# door_FM_rev_C.net
KiCad netlist of a schematic drawn in EAGLE
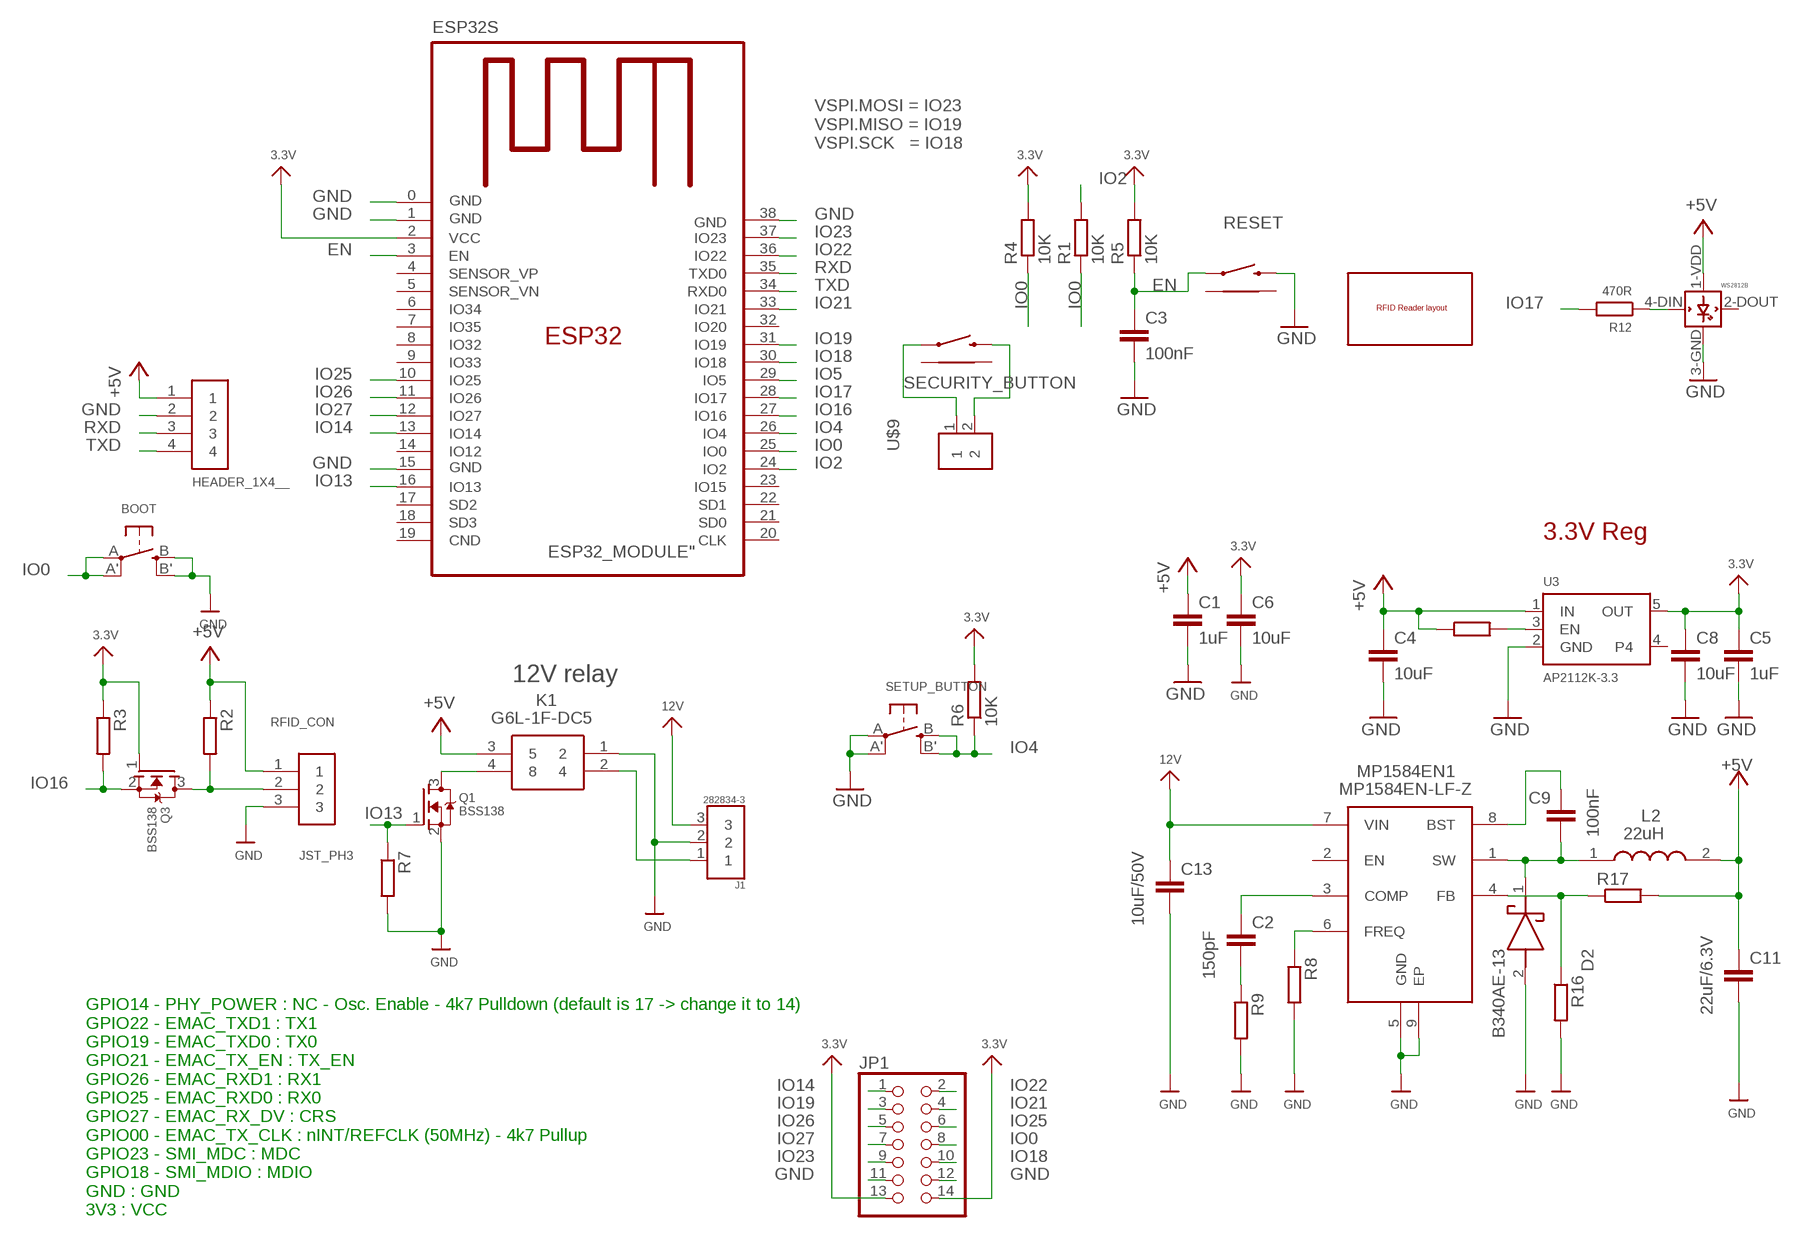
[diagram p0: schematic, sheet 1]

(export (version "E")
  (design (tool "Eeschema 10.0.6"))
  (components
    (comp (ref "BOOT")
      (value "BUTTON_KMR2_4.6X2.8")
      (footprint "eagle-import:BUTTON_KMR2_4.6X2.8")
      (libsource (lib "eagle-import") (part "BUTTON_KMR2_4.6X2.8"))
    )
    (comp (ref "C1")
      (value "1uF")
      (footprint "eagle-import:C0805")
      (libsource (lib "eagle-import") (part "C-EUC0805"))
    )
    (comp (ref "C2")
      (value "150pF")
      (footprint "eagle-import:C0805")
      (libsource (lib "eagle-import") (part "C-EUC0805"))
    )
    (comp (ref "C3")
      (value "100nF")
      (footprint "eagle-import:C0805")
      (libsource (lib "eagle-import") (part "C-EUC0805"))
    )
    (comp (ref "C4")
      (value "10uF")
      (footprint "eagle-import:C0805")
      (libsource (lib "eagle-import") (part "C-EUC0805"))
    )
    (comp (ref "C5")
      (value "1uF")
      (footprint "eagle-import:C0805")
      (libsource (lib "eagle-import") (part "C-EUC0805"))
    )
    (comp (ref "C6")
      (value "10uF")
      (footprint "eagle-import:C0805")
      (libsource (lib "eagle-import") (part "C-EUC0805"))
    )
    (comp (ref "C8")
      (value "10uF")
      (footprint "eagle-import:C0805")
      (libsource (lib "eagle-import") (part "C-EUC0805"))
    )
    (comp (ref "C9")
      (value "100nF")
      (footprint "eagle-import:C0805")
      (libsource (lib "eagle-import") (part "C-EUC0805"))
    )
    (comp (ref "C11")
      (value "22uF/6.3V")
      (footprint "eagle-import:C0805")
      (libsource (lib "eagle-import") (part "C-EUC0805"))
    )
    (comp (ref "C13")
      (value "10uF/50V")
      (footprint "eagle-import:C1206")
      (libsource (lib "eagle-import") (part "C-EUC1206"))
    )
    (comp (ref "CN1")
      (value "HEADER_1X4__")
      (footprint "eagle-import:HEADER_1X4_RIGHT_ANGLE")
      (libsource (lib "eagle-import") (part "HEADER_1X4__"))
    )
    (comp (ref "D2")
      (value "B340AE-13")
      (footprint "eagle-import:DIOM5226X240N")
      (fields (field (name "MOUSER_PART_NUMBER") "621-B340AE-13"))
      (libsource (lib "eagle-import") (part "B340AE-13"))
    )
    (comp (ref "ESP32S")
      (value "ESP32_MODULE\"")
      (footprint "eagle-import:ESP32_MODULE")
      (libsource (lib "eagle-import") (part "ESP32_MODULE{dblquote}"))
    )
    (comp (ref "J1")
      (value "282834-3")
      (footprint "eagle-import:TE_282834-3")
      (fields (field (name "MF") "TE Connectivity"))
      (libsource (lib "eagle-import") (part "282834-3"))
    )
    (comp (ref "JP1")
      (value "PINHD-2X7SMT")
      (footprint "eagle-import:2X07_SMT")
      (libsource (lib "eagle-import") (part "PINHD-2X7SMT"))
    )
    (comp (ref "K1")
      (value "G6L-1F-DC5")
      (footprint "eagle-import:G6L-1F-DC5")
      (fields (field (name "MOUSER_PART_NUMBER") "653-G6L-1F-DC5"))
      (libsource (lib "eagle-import") (part "G6L-1F-DC5"))
    )
    (comp (ref "L2")
      (value "22uH")
      (footprint "eagle-import:ASPI-0630LR")
      (fields
        (field (name "MANUFACTURER_PART_NUMBER") "ASPI-0630LR-4R7M-T15")
        (field (name "MOUSER_PART_NUMBER") "815-ASPI0630LR4R7T15")
      )
      (libsource (lib "eagle-import") (part "ASPI-0630LR-4R7M-T15"))
    )
    (comp (ref "MP1584EN1")
      (value "MP1584EN-LF-Z")
      (footprint "eagle-import:SOIC127P600X170-9N")
      (fields (field (name "MOUSER_PART_NUMBER") "946-MP1584ENLFZ"))
      (libsource (lib "eagle-import") (part "MP1584EN-LF-Z"))
    )
    (comp (ref "Q1")
      (value "BSS138")
      (footprint "eagle-import:SOT95P240X110-3")
      (libsource (lib "eagle-import") (part "MOSFET_N_"))
    )
    (comp (ref "Q3")
      (value "BSS138")
      (footprint "eagle-import:SOT95P240X110-3")
      (libsource (lib "eagle-import") (part "MOSFET_N_"))
    )
    (comp (ref "R1")
      (value "10K")
      (footprint "eagle-import:R0805")
      (libsource (lib "eagle-import") (part "R-EU_R0805"))
    )
    (comp (ref "R2")
      (value "10K")
      (footprint "eagle-import:R0805")
      (libsource (lib "eagle-import") (part "R-EU_R0805"))
    )
    (comp (ref "R3")
      (value "10K")
      (footprint "eagle-import:R0805")
      (libsource (lib "eagle-import") (part "R-EU_R0805"))
    )
    (comp (ref "R4")
      (value "10K")
      (footprint "eagle-import:R0805")
      (libsource (lib "eagle-import") (part "R-EU_R0805"))
    )
    (comp (ref "R5")
      (value "10K")
      (footprint "eagle-import:R0805")
      (libsource (lib "eagle-import") (part "R-EU_R0805"))
    )
    (comp (ref "R6")
      (value "10K")
      (footprint "eagle-import:R0805")
      (libsource (lib "eagle-import") (part "R-EU_R0805"))
    )
    (comp (ref "R7")
      (value "10K")
      (footprint "eagle-import:R0805")
      (libsource (lib "eagle-import") (part "R-EU_R0805"))
    )
    (comp (ref "R8")
      (value "100K")
      (footprint "eagle-import:R0805")
      (libsource (lib "eagle-import") (part "R-EU_R0805"))
    )
    (comp (ref "R9")
      (value "100K")
      (footprint "eagle-import:R0805")
      (libsource (lib "eagle-import") (part "R-EU_R0805"))
    )
    (comp (ref "R12")
      (value "470R")
      (footprint "eagle-import:R0805")
      (libsource (lib "eagle-import") (part "R-EU_R0805"))
    )
    (comp (ref "R16")
      (value "40K2")
      (footprint "eagle-import:R0805")
      (libsource (lib "eagle-import") (part "R-EU_R0805"))
    )
    (comp (ref "R17")
      (value "210K")
      (footprint "eagle-import:R0805")
      (libsource (lib "eagle-import") (part "R-EU_R0805"))
    )
    (comp (ref "R19")
      (value "10K")
      (footprint "eagle-import:R0805")
      (libsource (lib "eagle-import") (part "R-EU_R0805"))
    )
    (comp (ref "RESET")
      (value "TACTILE_SWITCH_RIGHT_ANGLE_THT_")
      (footprint "eagle-import:TACTILE_SWITCH_RIGHT_ANGLE_THT")
      (libsource (lib "eagle-import") (part "TACTILE_SWITCH_RIGHT_ANGLE_THT_"))
    )
    (comp (ref "RFID_CON")
      (value "JST_PH3")
      (footprint "eagle-import:JST-PH3")
      (libsource (lib "eagle-import") (part "JST_PH3"))
    )
    (comp (ref "SECURITY_BUTTON")
      (value "TACTILE_SWITCH_RIGHT_ANGLE_THT_")
      (footprint "eagle-import:TACTILE_SWITCH_RIGHT_ANGLE_THT")
      (libsource (lib "eagle-import") (part "TACTILE_SWITCH_RIGHT_ANGLE_THT_"))
    )
    (comp (ref "SETUP_BUTTON")
      (value "BUTTON_KMR2_4.6X2.8")
      (footprint "eagle-import:BUTTON_KMR2_4.6X2.8")
      (libsource (lib "eagle-import") (part "BUTTON_KMR2_4.6X2.8"))
    )
    (comp (ref "U$9")
      (value "282834-2")
      (footprint "eagle-import:CONN_282834-2")
      (fields (field (name "MF") "TE Connectivity"))
      (libsource (lib "eagle-import") (part "282834-2"))
    )
    (comp (ref "U$10")
      (value "RFID_READER")
      (footprint "eagle-import:RFID_READER")
      (libsource (lib "eagle-import") (part "RFID_READER"))
    )
    (comp (ref "U3")
      (value "AP2112K-3.3")
      (footprint "eagle-import:SOT95P290X120-5")
      (libsource (lib "eagle-import") (part "AP2112K-3.3_"))
    )
    (comp (ref "WS2812B")
      (value "WS2812B__")
      (footprint "eagle-import:WS2812B_5050")
      (libsource (lib "eagle-import") (part "WS2812B__"))
    )
  )
  (nets
    (net (code "1") (name "+5V") (class "Default")
      (node (ref "C1") (pin "1") (pinfunction "1_1") (pintype "passive"))
      (node (ref "C11") (pin "1") (pinfunction "1_1") (pintype "passive"))
      (node (ref "C4") (pin "1") (pinfunction "1_1") (pintype "passive"))
      (node (ref "CN1") (pin "1") (pinfunction "1_1") (pintype "bidirectional"))
      (node (ref "K1") (pin "3") (pinfunction "5_3") (pintype "bidirectional"))
      (node (ref "L2") (pin "2") (pinfunction "2_2") (pintype "bidirectional"))
      (node (ref "R17") (pin "2") (pinfunction "2_2") (pintype "passive"))
      (node (ref "R19") (pin "1") (pinfunction "1_1") (pintype "passive"))
      (node (ref "R2") (pin "1") (pinfunction "1_1") (pintype "passive"))
      (node (ref "RFID_CON") (pin "1") (pinfunction "1_1") (pintype "bidirectional"))
      (node (ref "U3") (pin "1") (pinfunction "IN_1") (pintype "bidirectional"))
      (node (ref "WS2812B") (pin "1-VDD") (pinfunction "VDD_1-VDD") (pintype "bidirectional"))
    )
    (net (code "2") (name "/EN") (class "Default")
      (node (ref "C3") (pin "1") (pinfunction "1_1") (pintype "passive"))
      (node (ref "ESP32S") (pin "3") (pinfunction "EN_3") (pintype "bidirectional"))
      (node (ref "R5") (pin "1") (pinfunction "1_1") (pintype "passive"))
      (node (ref "RESET") (pin "1") (pinfunction "1_1") (pintype "passive"))
    )
    (net (code "3") (name "/IO0") (class "Default")
      (node (ref "BOOT") (pin "A") (pinfunction "P_A") (pintype "passive"))
      (node (ref "BOOT") (pin "A'") (pinfunction "P1_A'") (pintype "passive"))
      (node (ref "ESP32S") (pin "25") (pinfunction "IO0_25") (pintype "bidirectional"))
      (node (ref "JP1") (pin "8") (pinfunction "8_8") (pintype "passive"))
      (node (ref "R1") (pin "1") (pinfunction "1_1") (pintype "passive"))
      (node (ref "R4") (pin "1") (pinfunction "1_1") (pintype "passive"))
    )
    (net (code "4") (name "/IO2") (class "Default")
      (node (ref "ESP32S") (pin "24") (pinfunction "IO2_24") (pintype "bidirectional"))
      (node (ref "R1") (pin "2") (pinfunction "2_2") (pintype "passive"))
    )
    (net (code "5") (name "/IO4") (class "Default")
      (node (ref "ESP32S") (pin "26") (pinfunction "IO4_26") (pintype "bidirectional"))
      (node (ref "R6") (pin "1") (pinfunction "1_1") (pintype "passive"))
      (node (ref "SETUP_BUTTON") (pin "B") (pinfunction "S_B") (pintype "passive"))
      (node (ref "SETUP_BUTTON") (pin "B'") (pinfunction "S1_B'") (pintype "passive"))
    )
    (net (code "6") (name "/IO5") (class "Default")
      (node (ref "ESP32S") (pin "29") (pinfunction "IO5_29") (pintype "bidirectional"))
    )
    (net (code "7") (name "/IO13") (class "Default")
      (node (ref "ESP32S") (pin "16") (pinfunction "IO13_16") (pintype "bidirectional"))
      (node (ref "Q1") (pin "1") (pinfunction "G_1") (pintype "bidirectional"))
      (node (ref "R7") (pin "1") (pinfunction "1_1") (pintype "passive"))
    )
    (net (code "8") (name "/IO14") (class "Default")
      (node (ref "ESP32S") (pin "13") (pinfunction "IO14_13") (pintype "bidirectional"))
      (node (ref "JP1") (pin "1") (pinfunction "1_1") (pintype "passive"))
    )
    (net (code "9") (name "/IO16") (class "Default")
      (node (ref "ESP32S") (pin "27") (pinfunction "IO16_27") (pintype "bidirectional"))
      (node (ref "Q3") (pin "2") (pinfunction "S_2") (pintype "bidirectional"))
      (node (ref "R3") (pin "2") (pinfunction "2_2") (pintype "passive"))
    )
    (net (code "10") (name "/IO17") (class "Default")
      (node (ref "ESP32S") (pin "28") (pinfunction "IO17_28") (pintype "bidirectional"))
      (node (ref "R12") (pin "2") (pinfunction "2_2") (pintype "passive"))
    )
    (net (code "11") (name "/IO18") (class "Default")
      (node (ref "ESP32S") (pin "30") (pinfunction "IO18_30") (pintype "bidirectional"))
      (node (ref "JP1") (pin "10") (pinfunction "10_10") (pintype "passive"))
    )
    (net (code "12") (name "/IO19") (class "Default")
      (node (ref "ESP32S") (pin "31") (pinfunction "IO19_31") (pintype "bidirectional"))
      (node (ref "JP1") (pin "3") (pinfunction "3_3") (pintype "passive"))
    )
    (net (code "13") (name "/IO21") (class "Default")
      (node (ref "ESP32S") (pin "33") (pinfunction "IO21_33") (pintype "bidirectional"))
      (node (ref "JP1") (pin "4") (pinfunction "4_4") (pintype "passive"))
    )
    (net (code "14") (name "/IO22") (class "Default")
      (node (ref "ESP32S") (pin "36") (pinfunction "IO22_36") (pintype "bidirectional"))
      (node (ref "JP1") (pin "2") (pinfunction "2_2") (pintype "passive"))
    )
    (net (code "15") (name "/IO23") (class "Default")
      (node (ref "ESP32S") (pin "37") (pinfunction "IO23_37") (pintype "bidirectional"))
      (node (ref "JP1") (pin "9") (pinfunction "9_9") (pintype "passive"))
    )
    (net (code "16") (name "/IO25") (class "Default")
      (node (ref "ESP32S") (pin "10") (pinfunction "IO25_10") (pintype "bidirectional"))
      (node (ref "JP1") (pin "6") (pinfunction "6_6") (pintype "passive"))
    )
    (net (code "17") (name "/IO26") (class "Default")
      (node (ref "ESP32S") (pin "11") (pinfunction "IO26_11") (pintype "bidirectional"))
      (node (ref "JP1") (pin "5") (pinfunction "5_5") (pintype "passive"))
    )
    (net (code "18") (name "/IO27") (class "Default")
      (node (ref "ESP32S") (pin "12") (pinfunction "IO27_12") (pintype "bidirectional"))
      (node (ref "JP1") (pin "7") (pinfunction "7_7") (pintype "passive"))
    )
    (net (code "19") (name "/RXD") (class "Default")
      (node (ref "CN1") (pin "3") (pinfunction "3_3") (pintype "bidirectional"))
      (node (ref "ESP32S") (pin "35") (pinfunction "TXD0_35") (pintype "bidirectional"))
    )
    (net (code "20") (name "/TXD") (class "Default")
      (node (ref "CN1") (pin "4") (pinfunction "4_4") (pintype "bidirectional"))
      (node (ref "ESP32S") (pin "34") (pinfunction "RXD0_34") (pintype "bidirectional"))
    )
    (net (code "21") (name "3.3V") (class "Default")
      (node (ref "C5") (pin "1") (pinfunction "1_1") (pintype "passive"))
      (node (ref "C6") (pin "1") (pinfunction "1_1") (pintype "passive"))
      (node (ref "C8") (pin "1") (pinfunction "1_1") (pintype "passive"))
      (node (ref "ESP32S") (pin "2") (pinfunction "VCC_2") (pintype "power_in"))
      (node (ref "JP1") (pin "13") (pinfunction "13_13") (pintype "passive"))
      (node (ref "JP1") (pin "14") (pinfunction "14_14") (pintype "passive"))
      (node (ref "Q3") (pin "1") (pinfunction "G_1") (pintype "bidirectional"))
      (node (ref "R3") (pin "1") (pinfunction "1_1") (pintype "passive"))
      (node (ref "R4") (pin "2") (pinfunction "2_2") (pintype "passive"))
      (node (ref "R5") (pin "2") (pinfunction "2_2") (pintype "passive"))
      (node (ref "R6") (pin "2") (pinfunction "2_2") (pintype "passive"))
      (node (ref "U3") (pin "5") (pinfunction "OUT_5") (pintype "bidirectional"))
    )
    (net (code "22") (name "12V") (class "Default")
      (node (ref "C13") (pin "1") (pinfunction "1_1") (pintype "passive"))
      (node (ref "J1") (pin "3") (pinfunction "3_3") (pintype "passive"))
      (node (ref "MP1584EN1") (pin "7") (pinfunction "VIN_7") (pintype "power_in"))
    )
    (net (code "23") (name "GND") (class "Default")
      (node (ref "BOOT") (pin "B") (pinfunction "S_B") (pintype "passive"))
      (node (ref "BOOT") (pin "B'") (pinfunction "S1_B'") (pintype "passive"))
      (node (ref "C1") (pin "2") (pinfunction "2_2") (pintype "passive"))
      (node (ref "C11") (pin "2") (pinfunction "2_2") (pintype "passive"))
      (node (ref "C13") (pin "2") (pinfunction "2_2") (pintype "passive"))
      (node (ref "C3") (pin "2") (pinfunction "2_2") (pintype "passive"))
      (node (ref "C4") (pin "2") (pinfunction "2_2") (pintype "passive"))
      (node (ref "C5") (pin "2") (pinfunction "2_2") (pintype "passive"))
      (node (ref "C6") (pin "2") (pinfunction "2_2") (pintype "passive"))
      (node (ref "C8") (pin "2") (pinfunction "2_2") (pintype "passive"))
      (node (ref "CN1") (pin "2") (pinfunction "2_2") (pintype "bidirectional"))
      (node (ref "D2") (pin "2") (pinfunction "A_2") (pintype "bidirectional"))
      (node (ref "ESP32S") (pin "0") (pinfunction "GND_0") (pintype "power_in"))
      (node (ref "ESP32S") (pin "1") (pinfunction "GND_1") (pintype "power_in"))
      (node (ref "ESP32S") (pin "15") (pinfunction "GND_15") (pintype "power_in"))
      (node (ref "ESP32S") (pin "38") (pinfunction "GND_38") (pintype "power_in"))
      (node (ref "J1") (pin "2") (pinfunction "2_2") (pintype "passive"))
      (node (ref "JP1") (pin "11") (pinfunction "11_11") (pintype "passive"))
      (node (ref "JP1") (pin "12") (pinfunction "12_12") (pintype "passive"))
      (node (ref "K1") (pin "1") (pinfunction "2_1") (pintype "bidirectional"))
      (node (ref "MP1584EN1") (pin "5") (pinfunction "GND_5") (pintype "power_in"))
      (node (ref "MP1584EN1") (pin "9") (pinfunction "EP_9") (pintype "bidirectional"))
      (node (ref "Q1") (pin "2") (pinfunction "S_2") (pintype "bidirectional"))
      (node (ref "R16") (pin "2") (pinfunction "2_2") (pintype "passive"))
      (node (ref "R7") (pin "2") (pinfunction "2_2") (pintype "passive"))
      (node (ref "R8") (pin "2") (pinfunction "2_2") (pintype "passive"))
      (node (ref "R9") (pin "2") (pinfunction "2_2") (pintype "passive"))
      (node (ref "RESET") (pin "2") (pinfunction "2_2") (pintype "passive"))
      (node (ref "RFID_CON") (pin "3") (pinfunction "3_3") (pintype "bidirectional"))
      (node (ref "SETUP_BUTTON") (pin "A") (pinfunction "P_A") (pintype "passive"))
      (node (ref "SETUP_BUTTON") (pin "A'") (pinfunction "P1_A'") (pintype "passive"))
      (node (ref "U3") (pin "2") (pinfunction "GND_2") (pintype "bidirectional"))
      (node (ref "WS2812B") (pin "3-GND") (pinfunction "GND_3-GND") (pintype "bidirectional"))
    )
    (net (code "24") (name "Net-(C2-Pad2)") (class "Default")
      (node (ref "C2") (pin "2") (pinfunction "2_2") (pintype "passive"))
      (node (ref "R9") (pin "1") (pinfunction "1_1") (pintype "passive"))
    )
    (net (code "25") (name "Net-(D2-K)") (class "Default")
      (node (ref "C9") (pin "2") (pinfunction "2_2") (pintype "passive"))
      (node (ref "D2") (pin "1") (pinfunction "K_1") (pintype "bidirectional"))
      (node (ref "L2") (pin "1") (pinfunction "1_1") (pintype "bidirectional"))
      (node (ref "MP1584EN1") (pin "1") (pinfunction "SW_1") (pintype "output"))
    )
    (net (code "26") (name "Net-(K1-4)") (class "Default")
      (node (ref "J1") (pin "1") (pinfunction "1_1") (pintype "passive"))
      (node (ref "K1") (pin "2") (pinfunction "4_2") (pintype "bidirectional"))
    )
    (net (code "27") (name "Net-(K1-8)") (class "Default")
      (node (ref "K1") (pin "4") (pinfunction "8_4") (pintype "bidirectional"))
      (node (ref "Q1") (pin "3") (pinfunction "D_3") (pintype "bidirectional"))
    )
    (net (code "28") (name "Net-(MP1584EN1-BST)") (class "Default")
      (node (ref "C9") (pin "1") (pinfunction "1_1") (pintype "passive"))
      (node (ref "MP1584EN1") (pin "8") (pinfunction "BST_8") (pintype "input"))
    )
    (net (code "29") (name "Net-(MP1584EN1-COMP)") (class "Default")
      (node (ref "C2") (pin "1") (pinfunction "1_1") (pintype "passive"))
      (node (ref "MP1584EN1") (pin "3") (pinfunction "COMP_3") (pintype "bidirectional"))
    )
    (net (code "30") (name "Net-(MP1584EN1-FB)") (class "Default")
      (node (ref "MP1584EN1") (pin "4") (pinfunction "FB_4") (pintype "input"))
      (node (ref "R16") (pin "1") (pinfunction "1_1") (pintype "passive"))
      (node (ref "R17") (pin "1") (pinfunction "1_1") (pintype "passive"))
    )
    (net (code "31") (name "Net-(MP1584EN1-FREQ)") (class "Default")
      (node (ref "MP1584EN1") (pin "6") (pinfunction "FREQ_6") (pintype "input"))
      (node (ref "R8") (pin "1") (pinfunction "1_1") (pintype "passive"))
    )
    (net (code "32") (name "Net-(Q3-D)") (class "Default")
      (node (ref "Q3") (pin "3") (pinfunction "D_3") (pintype "bidirectional"))
      (node (ref "R2") (pin "2") (pinfunction "2_2") (pintype "passive"))
      (node (ref "RFID_CON") (pin "2") (pinfunction "2_2") (pintype "bidirectional"))
    )
    (net (code "33") (name "Net-(SECURITY_BUTTON-Pad1)") (class "Default")
      (node (ref "SECURITY_BUTTON") (pin "1") (pinfunction "1_1") (pintype "passive"))
      (node (ref "U$9") (pin "1") (pinfunction "1_1") (pintype "passive"))
    )
    (net (code "34") (name "Net-(SECURITY_BUTTON-Pad2)") (class "Default")
      (node (ref "SECURITY_BUTTON") (pin "2") (pinfunction "2_2") (pintype "passive"))
      (node (ref "U$9") (pin "2") (pinfunction "2_2") (pintype "passive"))
    )
    (net (code "35") (name "Net-(U3-EN)") (class "Default")
      (node (ref "R19") (pin "2") (pinfunction "2_2") (pintype "passive"))
      (node (ref "U3") (pin "3") (pinfunction "EN_3") (pintype "bidirectional"))
    )
    (net (code "36") (name "Net-(WS2812B-DIN)") (class "Default")
      (node (ref "R12") (pin "1") (pinfunction "1_1") (pintype "passive"))
      (node (ref "WS2812B") (pin "4-DIN") (pinfunction "DIN_4-DIN") (pintype "input"))
    )
    (net (code "37") (name "unconnected-(ESP32S-CLK-Pad20)") (class "Default")
      (node (ref "ESP32S") (pin "20") (pinfunction "CLK_20") (pintype "bidirectional"))
    )
    (net (code "38") (name "unconnected-(ESP32S-CND-Pad19)") (class "Default")
      (node (ref "ESP32S") (pin "19") (pinfunction "CND_19") (pintype "bidirectional"))
    )
    (net (code "39") (name "unconnected-(ESP32S-IO12-Pad14)") (class "Default")
      (node (ref "ESP32S") (pin "14") (pinfunction "IO12_14") (pintype "bidirectional"))
    )
    (net (code "40") (name "unconnected-(ESP32S-IO15-Pad23)") (class "Default")
      (node (ref "ESP32S") (pin "23") (pinfunction "IO15_23") (pintype "bidirectional"))
    )
    (net (code "41") (name "unconnected-(ESP32S-IO20-Pad32)") (class "Default")
      (node (ref "ESP32S") (pin "32") (pinfunction "IO20_32") (pintype "bidirectional"))
    )
    (net (code "42") (name "unconnected-(ESP32S-IO32-Pad8)") (class "Default")
      (node (ref "ESP32S") (pin "8") (pinfunction "IO32_8") (pintype "bidirectional"))
    )
    (net (code "43") (name "unconnected-(ESP32S-IO33-Pad9)") (class "Default")
      (node (ref "ESP32S") (pin "9") (pinfunction "IO33_9") (pintype "bidirectional"))
    )
    (net (code "44") (name "unconnected-(ESP32S-IO34-Pad6)") (class "Default")
      (node (ref "ESP32S") (pin "6") (pinfunction "IO34_6") (pintype "bidirectional"))
    )
    (net (code "45") (name "unconnected-(ESP32S-IO35-Pad7)") (class "Default")
      (node (ref "ESP32S") (pin "7") (pinfunction "IO35_7") (pintype "bidirectional"))
    )
    (net (code "46") (name "unconnected-(ESP32S-SD0-Pad21)") (class "Default")
      (node (ref "ESP32S") (pin "21") (pinfunction "SD0_21") (pintype "bidirectional"))
    )
    (net (code "47") (name "unconnected-(ESP32S-SD1-Pad22)") (class "Default")
      (node (ref "ESP32S") (pin "22") (pinfunction "SD1_22") (pintype "bidirectional"))
    )
    (net (code "48") (name "unconnected-(ESP32S-SD2-Pad17)") (class "Default")
      (node (ref "ESP32S") (pin "17") (pinfunction "SD2_17") (pintype "bidirectional"))
    )
    (net (code "49") (name "unconnected-(ESP32S-SD3-Pad18)") (class "Default")
      (node (ref "ESP32S") (pin "18") (pinfunction "SD3_18") (pintype "bidirectional"))
    )
    (net (code "50") (name "unconnected-(ESP32S-SENSOR_VN-Pad5)") (class "Default")
      (node (ref "ESP32S") (pin "5") (pinfunction "SENSOR_VN_5") (pintype "bidirectional"))
    )
    (net (code "51") (name "unconnected-(ESP32S-SENSOR_VP-Pad4)") (class "Default")
      (node (ref "ESP32S") (pin "4") (pinfunction "SENSOR_VP_4") (pintype "bidirectional"))
    )
    (net (code "52") (name "unconnected-(MP1584EN1-EN-Pad2)") (class "Default")
      (node (ref "MP1584EN1") (pin "2") (pinfunction "EN_2") (pintype "input"))
    )
    (net (code "53") (name "unconnected-(RESET-3-PadANCHOR1)") (class "Default")
      (node (ref "RESET") (pin "ANCHOR1") (pinfunction "3_ANCHOR1") (pintype "passive"))
    )
    (net (code "54") (name "unconnected-(RESET-4-PadANCHOR2)") (class "Default")
      (node (ref "RESET") (pin "ANCHOR2") (pinfunction "4_ANCHOR2") (pintype "passive"))
    )
    (net (code "55") (name "unconnected-(SECURITY_BUTTON-3-PadANCHOR1)") (class "Default")
      (node (ref "SECURITY_BUTTON") (pin "ANCHOR1") (pinfunction "3_ANCHOR1") (pintype "passive"))
    )
    (net (code "56") (name "unconnected-(SECURITY_BUTTON-4-PadANCHOR2)") (class "Default")
      (node (ref "SECURITY_BUTTON") (pin "ANCHOR2") (pinfunction "4_ANCHOR2") (pintype "passive"))
    )
    (net (code "57") (name "unconnected-(U3-P4-Pad4)") (class "Default")
      (node (ref "U3") (pin "4") (pinfunction "P4_4") (pintype "bidirectional"))
    )
    (net (code "58") (name "unconnected-(WS2812B-DOUT-Pad2-DOUT)") (class "Default")
      (node (ref "WS2812B") (pin "2-DOUT") (pinfunction "DOUT_2-DOUT") (pintype "output"))
    )
  )
)
